# Power.net
KiCad netlist of a schematic drawn in Altium Designer
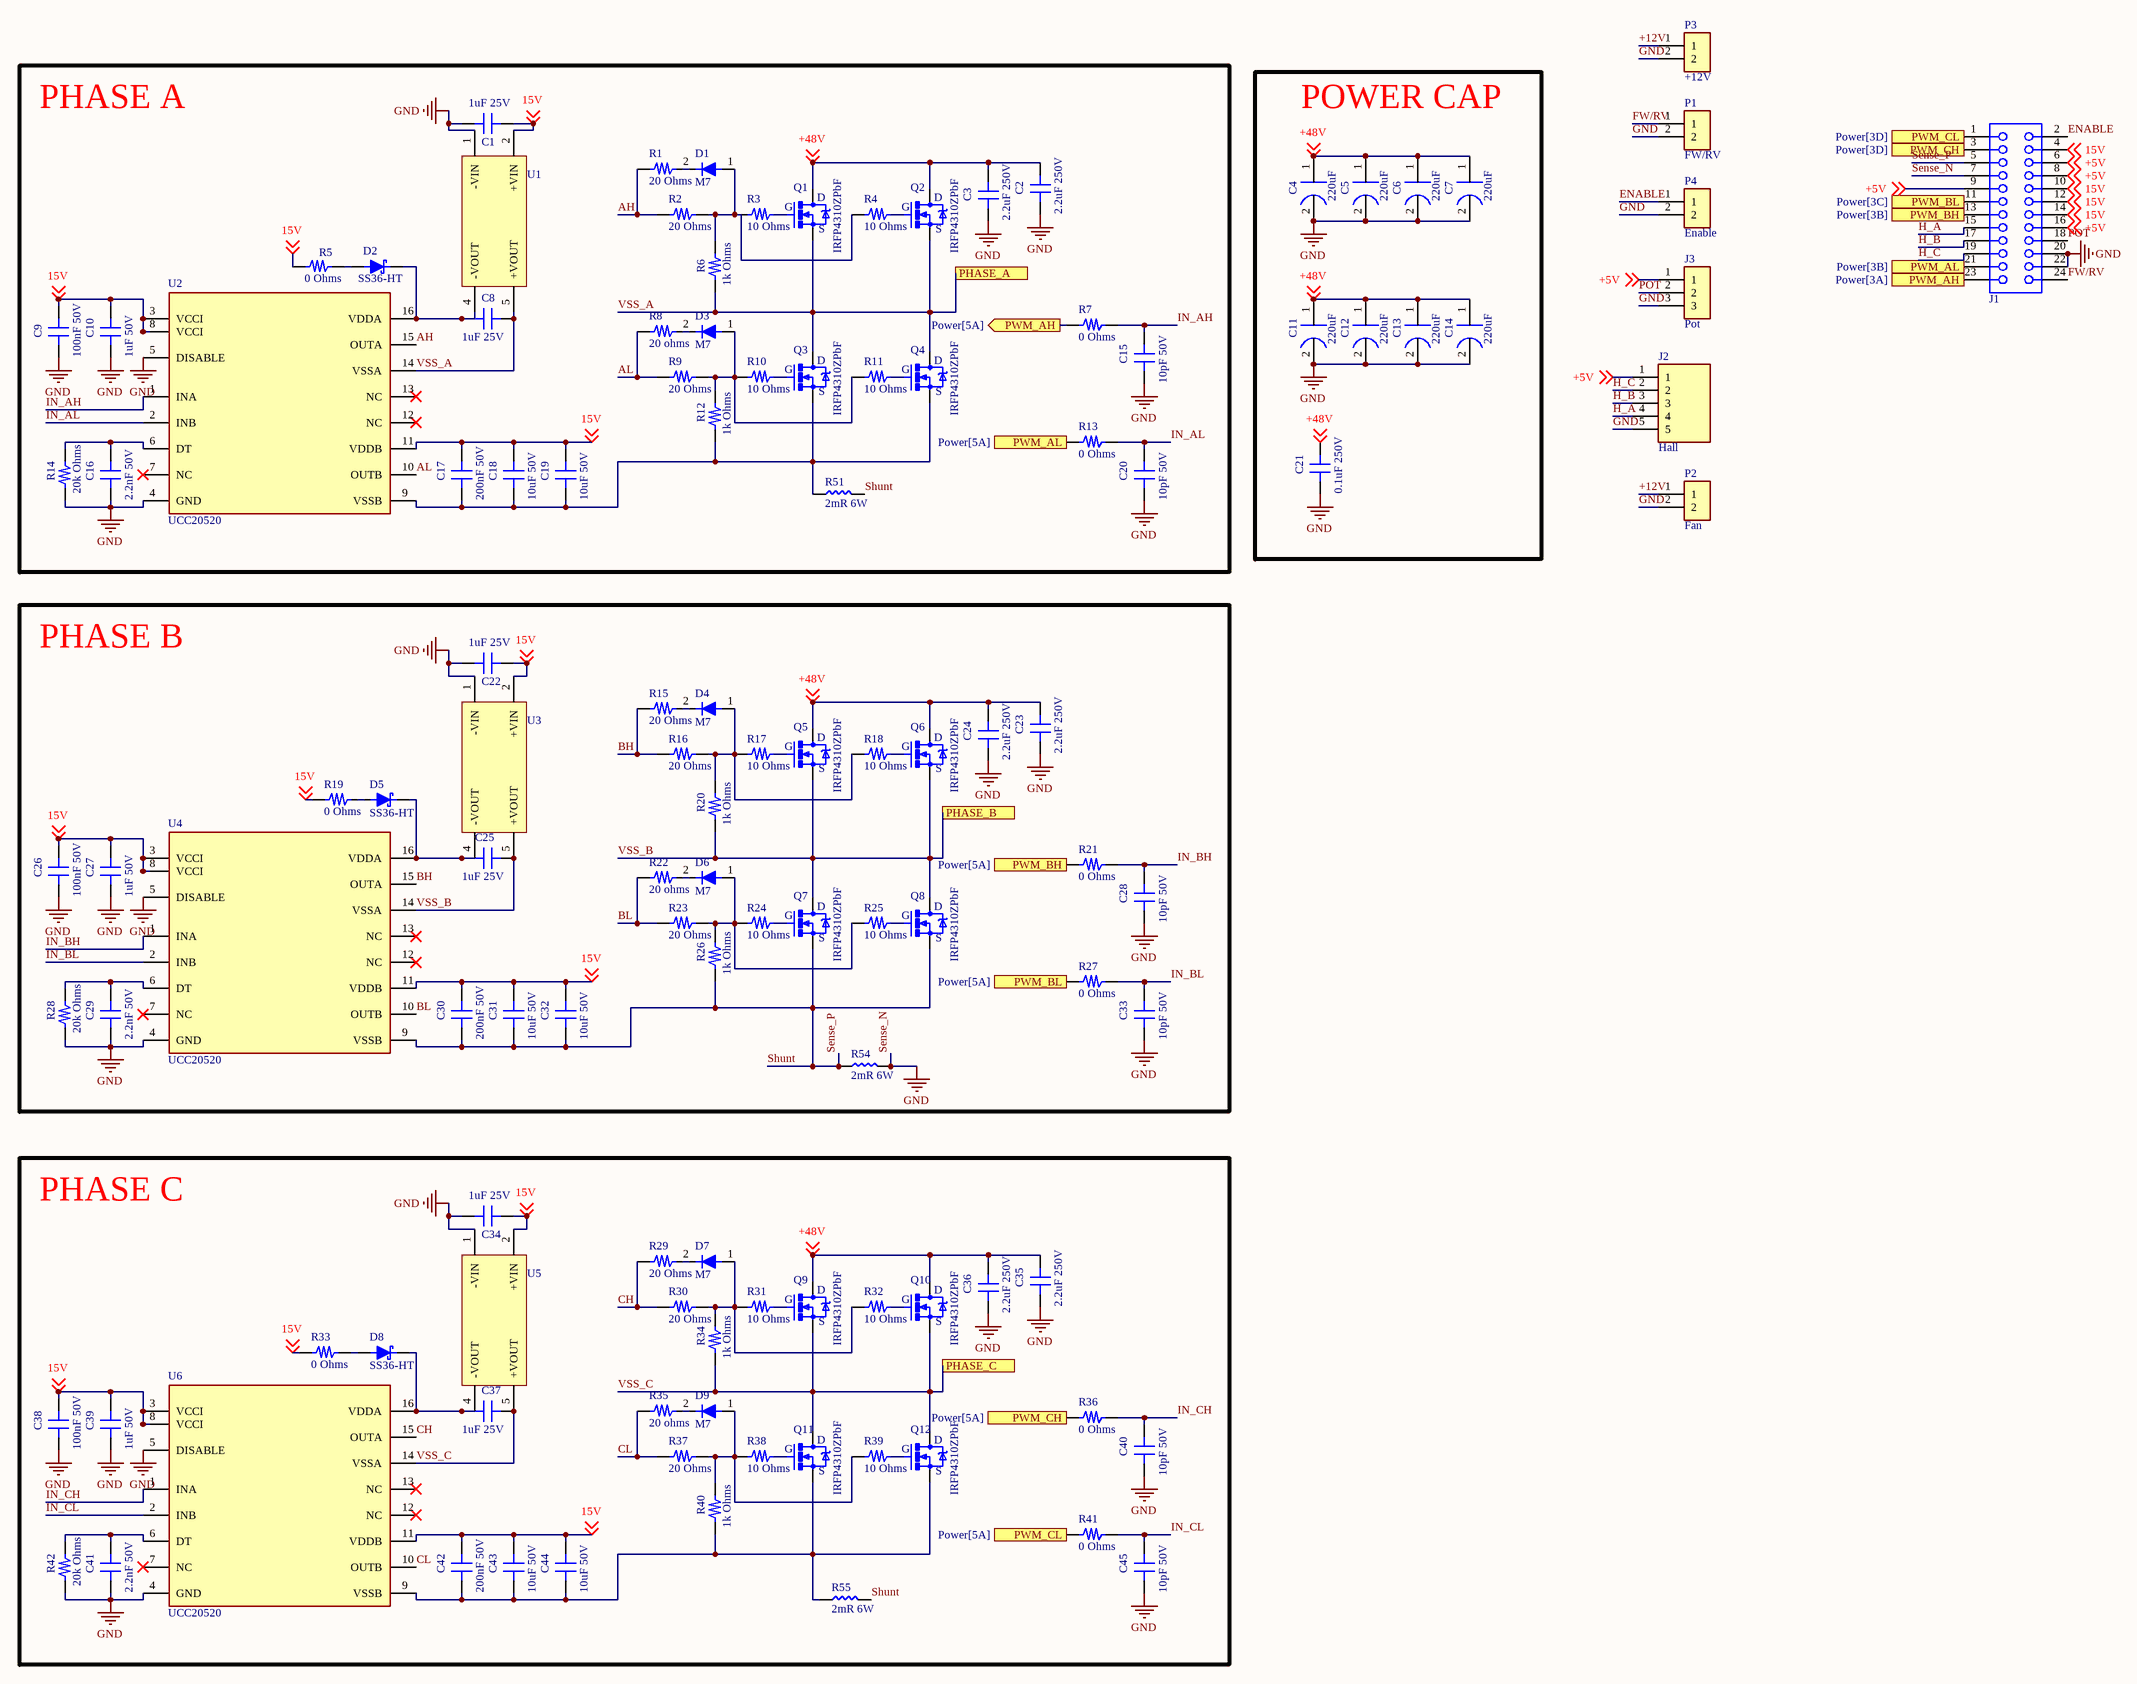
[diagram p0: Power.SchDoc]

(export (version "E")
  (design (tool "Eeschema 10.0.6"))
  (components
    (comp (ref "C1")
      (value "1uF 25V")
      (footprint "0805_CAP")
      (description "1-3.3 uF polyster film cap")
      (libsource (lib "HidroanaSCHLib1") (part "CAP_0805"))
    )
    (comp (ref "C2")
      (value "2.2uF 250V")
      (footprint "0805_CAP")
      (description "MLCC")
      (libsource (lib "HidroanaSCHLib1") (part "CAP_0805"))
    )
    (comp (ref "C3")
      (value "2.2uF 250V")
      (footprint "0805_CAP")
      (description "MLCC")
      (libsource (lib "HidroanaSCHLib1") (part "CAP_0805"))
    )
    (comp (ref "C4")
      (value "220uF")
      (footprint "220uF 100V Cap")
      (libsource (lib "Hidroana Lib") (part "220uF 100V Cap"))
    )
    (comp (ref "C5")
      (value "220uF")
      (footprint "220uF 100V Cap")
      (libsource (lib "Hidroana Lib") (part "220uF 100V Cap"))
    )
    (comp (ref "C6")
      (value "220uF")
      (footprint "220uF 100V Cap")
      (libsource (lib "Hidroana Lib") (part "220uF 100V Cap"))
    )
    (comp (ref "C7")
      (value "220uF")
      (footprint "220uF 100V Cap")
      (libsource (lib "Hidroana Lib") (part "220uF 100V Cap"))
    )
    (comp (ref "C8")
      (value "1uF 25V")
      (footprint "0805_CAP")
      (libsource (lib "HidroanaSCHLib1") (part "CAP_0805"))
    )
    (comp (ref "C9")
      (value "100nF 50V")
      (footprint "0805_CAP")
      (description "MLCC")
      (libsource (lib "HidroanaSCHLib1") (part "CAP_0805"))
    )
    (comp (ref "C10")
      (value "1uF 50V")
      (footprint "0805_CAP")
      (description "tantalum or electrolytic")
      (libsource (lib "HidroanaSCHLib1") (part "CAP_0805"))
    )
    (comp (ref "C11")
      (value "220uF")
      (footprint "220uF 100V Cap")
      (libsource (lib "Hidroana Lib") (part "220uF 100V Cap"))
    )
    (comp (ref "C12")
      (value "220uF")
      (footprint "220uF 100V Cap")
      (libsource (lib "Hidroana Lib") (part "220uF 100V Cap"))
    )
    (comp (ref "C13")
      (value "220uF")
      (footprint "220uF 100V Cap")
      (libsource (lib "Hidroana Lib") (part "220uF 100V Cap"))
    )
    (comp (ref "C14")
      (value "220uF")
      (footprint "220uF 100V Cap")
      (libsource (lib "Hidroana Lib") (part "220uF 100V Cap"))
    )
    (comp (ref "C15")
      (value "10pF 50V")
      (footprint "0805_CAP")
      (description "MLCC 10-100 pF")
      (libsource (lib "HidroanaSCHLib1") (part "CAP_0805"))
    )
    (comp (ref "C16")
      (value "2.2nF 50V")
      (footprint "0805_CAP")
      (libsource (lib "HidroanaSCHLib1") (part "CAP_0805"))
    )
    (comp (ref "C17")
      (value "200nF 50V")
      (footprint "0805_CAP")
      (description "MLCC")
      (libsource (lib "HidroanaSCHLib1") (part "CAP_0805"))
    )
    (comp (ref "C18")
      (value "10uF 50V")
      (footprint "0805_CAP")
      (description "MLCC")
      (libsource (lib "HidroanaSCHLib1") (part "CAP_0805"))
    )
    (comp (ref "C19")
      (value "10uF 50V")
      (footprint "0805_CAP")
      (description "tantalum or electrolytic")
      (libsource (lib "HidroanaSCHLib1") (part "CAP_0805"))
    )
    (comp (ref "C20")
      (value "10pF 50V")
      (footprint "0805_CAP")
      (description "MLCC 10-100 pF")
      (libsource (lib "HidroanaSCHLib1") (part "CAP_0805"))
    )
    (comp (ref "C21")
      (value "0.1uF 250V")
      (footprint "0805_CAP")
      (description "MLCC")
      (libsource (lib "HidroanaSCHLib1") (part "CAP_0805"))
    )
    (comp (ref "C22")
      (value "1uF 25V")
      (footprint "0805_CAP")
      (description "1-3.3 uF polyster film cap")
      (libsource (lib "HidroanaSCHLib1") (part "CAP_0805"))
    )
    (comp (ref "C23")
      (value "2.2uF 250V")
      (footprint "0805_CAP")
      (description "MLCC")
      (libsource (lib "HidroanaSCHLib1") (part "CAP_0805"))
    )
    (comp (ref "C24")
      (value "2.2uF 250V")
      (footprint "0805_CAP")
      (description "MLCC")
      (libsource (lib "HidroanaSCHLib1") (part "CAP_0805"))
    )
    (comp (ref "C25")
      (value "1uF 25V")
      (footprint "0805_CAP")
      (libsource (lib "HidroanaSCHLib1") (part "CAP_0805"))
    )
    (comp (ref "C26")
      (value "100nF 50V")
      (footprint "0805_CAP")
      (description "MLCC")
      (libsource (lib "HidroanaSCHLib1") (part "CAP_0805"))
    )
    (comp (ref "C27")
      (value "1uF 50V")
      (footprint "0805_CAP")
      (description "tantalum or electrolytic")
      (libsource (lib "HidroanaSCHLib1") (part "CAP_0805"))
    )
    (comp (ref "C28")
      (value "10pF 50V")
      (footprint "0805_CAP")
      (description "MLCC 10-100 pF")
      (libsource (lib "HidroanaSCHLib1") (part "CAP_0805"))
    )
    (comp (ref "C29")
      (value "2.2nF 50V")
      (footprint "0805_CAP")
      (libsource (lib "HidroanaSCHLib1") (part "CAP_0805"))
    )
    (comp (ref "C30")
      (value "200nF 50V")
      (footprint "0805_CAP")
      (description "MLCC")
      (libsource (lib "HidroanaSCHLib1") (part "CAP_0805"))
    )
    (comp (ref "C31")
      (value "10uF 50V")
      (footprint "0805_CAP")
      (description "MLCC")
      (libsource (lib "HidroanaSCHLib1") (part "CAP_0805"))
    )
    (comp (ref "C32")
      (value "10uF 50V")
      (footprint "0805_CAP")
      (description "tantalum or electrolytic")
      (libsource (lib "HidroanaSCHLib1") (part "CAP_0805"))
    )
    (comp (ref "C33")
      (value "10pF 50V")
      (footprint "0805_CAP")
      (description "MLCC 10-100 pF")
      (libsource (lib "HidroanaSCHLib1") (part "CAP_0805"))
    )
    (comp (ref "C34")
      (value "1uF 25V")
      (footprint "0805_CAP")
      (description "1-3.3 uF polyster film cap")
      (libsource (lib "HidroanaSCHLib1") (part "CAP_0805"))
    )
    (comp (ref "C35")
      (value "2.2uF 250V")
      (footprint "0805_CAP")
      (description "MLCC")
      (libsource (lib "HidroanaSCHLib1") (part "CAP_0805"))
    )
    (comp (ref "C36")
      (value "2.2uF 250V")
      (footprint "0805_CAP")
      (description "MLCC")
      (libsource (lib "HidroanaSCHLib1") (part "CAP_0805"))
    )
    (comp (ref "C37")
      (value "1uF 25V")
      (footprint "0805_CAP")
      (libsource (lib "HidroanaSCHLib1") (part "CAP_0805"))
    )
    (comp (ref "C38")
      (value "100nF 50V")
      (footprint "0805_CAP")
      (description "MLCC")
      (libsource (lib "HidroanaSCHLib1") (part "CAP_0805"))
    )
    (comp (ref "C39")
      (value "1uF 50V")
      (footprint "0805_CAP")
      (description "tantalum or electrolytic")
      (libsource (lib "HidroanaSCHLib1") (part "CAP_0805"))
    )
    (comp (ref "C40")
      (value "10pF 50V")
      (footprint "0805_CAP")
      (description "MLCC 10-100 pF")
      (libsource (lib "HidroanaSCHLib1") (part "CAP_0805"))
    )
    (comp (ref "C41")
      (value "2.2nF 50V")
      (footprint "0805_CAP")
      (libsource (lib "HidroanaSCHLib1") (part "CAP_0805"))
    )
    (comp (ref "C42")
      (value "200nF 50V")
      (footprint "0805_CAP")
      (description "MLCC")
      (libsource (lib "HidroanaSCHLib1") (part "CAP_0805"))
    )
    (comp (ref "C43")
      (value "10uF 50V")
      (footprint "0805_CAP")
      (description "MLCC")
      (libsource (lib "HidroanaSCHLib1") (part "CAP_0805"))
    )
    (comp (ref "C44")
      (value "10uF 50V")
      (footprint "0805_CAP")
      (description "tantalum or electrolytic")
      (libsource (lib "HidroanaSCHLib1") (part "CAP_0805"))
    )
    (comp (ref "C45")
      (value "10pF 50V")
      (footprint "0805_CAP")
      (description "MLCC 10-100 pF")
      (libsource (lib "HidroanaSCHLib1") (part "CAP_0805"))
    )
    (comp (ref "D1")
      (value "M7")
      (footprint "DIOM5025X220N")
      (description "M7-DC - DIODE STAND. Single 1A 1000V SMT DO214AC (SMA)")
      (libsource (lib "HidroanaSCHLib1") (part "M7"))
    )
    (comp (ref "D2")
      (value "SS36-HT")
      (footprint "DO-214AB")
      (description "Schottky Diode")
      (libsource (lib "HidroanaSCHLib1") (part "SS36-214AB-HT"))
    )
    (comp (ref "D3")
      (value "M7")
      (footprint "DIOM5025X220N")
      (description "M7-DC - DIODE STAND. Single 1A 1000V SMT DO214AC (SMA)")
      (libsource (lib "HidroanaSCHLib1") (part "M7"))
    )
    (comp (ref "D4")
      (value "M7")
      (footprint "DIOM5025X220N")
      (description "M7-DC - DIODE STAND. Single 1A 1000V SMT DO214AC (SMA)")
      (libsource (lib "HidroanaSCHLib1") (part "M7"))
    )
    (comp (ref "D5")
      (value "SS36-HT")
      (footprint "DO-214AB")
      (description "Schottky Diode")
      (libsource (lib "HidroanaSCHLib1") (part "SS36-214AB-HT"))
    )
    (comp (ref "D6")
      (value "M7")
      (footprint "DIOM5025X220N")
      (description "M7-DC - DIODE STAND. Single 1A 1000V SMT DO214AC (SMA)")
      (libsource (lib "HidroanaSCHLib1") (part "M7"))
    )
    (comp (ref "D7")
      (value "M7")
      (footprint "DIOM5025X220N")
      (description "M7-DC - DIODE STAND. Single 1A 1000V SMT DO214AC (SMA)")
      (libsource (lib "HidroanaSCHLib1") (part "M7"))
    )
    (comp (ref "D8")
      (value "SS36-HT")
      (footprint "DO-214AB")
      (description "Schottky Diode")
      (libsource (lib "HidroanaSCHLib1") (part "SS36-214AB-HT"))
    )
    (comp (ref "D9")
      (value "M7")
      (footprint "DIOM5025X220N")
      (description "M7-DC - DIODE STAND. Single 1A 1000V SMT DO214AC (SMA)")
      (libsource (lib "HidroanaSCHLib1") (part "M7"))
    )
    (comp (ref "J1")
      (value "61302421821")
      (footprint "61302421821")
      (description "WR-PHD Socket Header, THT, Vertical, pitch 2.54mm, 2 Row, 24P")
      (fields (field (name "MANUFACTURER") "Wurth Elektronik"))
      (libsource (lib "Altium_WR-PHD (rev24a) (1)") (part "61302421821"))
    )
    (comp (ref "J2")
      (value "Hall")
      (footprint "TE_282837-5")
      (description "TERMI-BLOK PCB MOUNT 5P")
      (fields (field (name "MP") "282837-5") (field (name "MF") "TE Connectivity"))
      (libsource (lib "TBLOCK-I5") (part "282837-5"))
    )
    (comp (ref "J3")
      (value "Pot")
      (footprint "TE_282837-3")
      (description "TERMI-BLOK PCB MOUNT 3P")
      (fields (field (name "MP") "282837-3"))
      (libsource (lib "TBLOCK-I3") (part "282837-3"))
    )
    (comp (ref "P1")
      (value "FW/RV")
      (footprint "TE_282837-2")
      (fields (field (name "MF") "TE Connectivity") (field (name "MP") "282837-2"))
      (libsource (lib "TBLOCK-I2") (part "282837-2"))
    )
    (comp (ref "P2")
      (value "Fan")
      (footprint "TE_282837-2")
      (fields (field (name "MF") "TE Connectivity") (field (name "MP") "282837-2"))
      (libsource (lib "TBLOCK-I2") (part "282837-2"))
    )
    (comp (ref "P3")
      (value "+12V")
      (footprint "TE_282837-2")
      (fields (field (name "MF") "TE Connectivity") (field (name "MP") "282837-2"))
      (libsource (lib "TBLOCK-I2") (part "282837-2"))
    )
    (comp (ref "P4")
      (value "Enable")
      (footprint "TE_282837-2")
      (fields (field (name "MF") "TE Connectivity") (field (name "MP") "282837-2"))
      (libsource (lib "TBLOCK-I2") (part "282837-2"))
    )
    (comp (ref "Q1")
      (value "IRFP4310ZPbF")
      (footprint "TO-247")
      (description "IRFP4310ZPBF - MOSFET DIS.120A 100V N-CH TO247AC HEXFET THT")
      (libsource (lib "HidroanaSCHLib1") (part "IRFP4310ZPbF"))
    )
    (comp (ref "Q2")
      (value "IRFP4310ZPbF")
      (footprint "TO-247")
      (description "IRFP4310ZPBF - MOSFET DIS.120A 100V N-CH TO247AC HEXFET THT")
      (libsource (lib "HidroanaSCHLib1") (part "IRFP4310ZPbF"))
    )
    (comp (ref "Q3")
      (value "IRFP4310ZPbF")
      (footprint "TO-247")
      (description "IRFP4310ZPBF - MOSFET DIS.120A 100V N-CH TO247AC HEXFET THT")
      (libsource (lib "HidroanaSCHLib1") (part "IRFP4310ZPbF"))
    )
    (comp (ref "Q4")
      (value "IRFP4310ZPbF")
      (footprint "TO-247")
      (description "IRFP4310ZPBF - MOSFET DIS.120A 100V N-CH TO247AC HEXFET THT")
      (libsource (lib "HidroanaSCHLib1") (part "IRFP4310ZPbF"))
    )
    (comp (ref "Q5")
      (value "IRFP4310ZPbF")
      (footprint "TO-247")
      (description "IRFP4310ZPBF - MOSFET DIS.120A 100V N-CH TO247AC HEXFET THT")
      (libsource (lib "HidroanaSCHLib1") (part "IRFP4310ZPbF"))
    )
    (comp (ref "Q6")
      (value "IRFP4310ZPbF")
      (footprint "TO-247")
      (description "IRFP4310ZPBF - MOSFET DIS.120A 100V N-CH TO247AC HEXFET THT")
      (libsource (lib "HidroanaSCHLib1") (part "IRFP4310ZPbF"))
    )
    (comp (ref "Q7")
      (value "IRFP4310ZPbF")
      (footprint "TO-247")
      (description "IRFP4310ZPBF - MOSFET DIS.120A 100V N-CH TO247AC HEXFET THT")
      (libsource (lib "HidroanaSCHLib1") (part "IRFP4310ZPbF"))
    )
    (comp (ref "Q8")
      (value "IRFP4310ZPbF")
      (footprint "TO-247")
      (description "IRFP4310ZPBF - MOSFET DIS.120A 100V N-CH TO247AC HEXFET THT")
      (libsource (lib "HidroanaSCHLib1") (part "IRFP4310ZPbF"))
    )
    (comp (ref "Q9")
      (value "IRFP4310ZPbF")
      (footprint "TO-247")
      (description "IRFP4310ZPBF - MOSFET DIS.120A 100V N-CH TO247AC HEXFET THT")
      (libsource (lib "HidroanaSCHLib1") (part "IRFP4310ZPbF"))
    )
    (comp (ref "Q10")
      (value "IRFP4310ZPbF")
      (footprint "TO-247")
      (description "IRFP4310ZPBF - MOSFET DIS.120A 100V N-CH TO247AC HEXFET THT")
      (libsource (lib "HidroanaSCHLib1") (part "IRFP4310ZPbF"))
    )
    (comp (ref "Q11")
      (value "IRFP4310ZPbF")
      (footprint "TO-247")
      (description "IRFP4310ZPBF - MOSFET DIS.120A 100V N-CH TO247AC HEXFET THT")
      (libsource (lib "HidroanaSCHLib1") (part "IRFP4310ZPbF"))
    )
    (comp (ref "Q12")
      (value "IRFP4310ZPbF")
      (footprint "TO-247")
      (description "IRFP4310ZPBF - MOSFET DIS.120A 100V N-CH TO247AC HEXFET THT")
      (libsource (lib "HidroanaSCHLib1") (part "IRFP4310ZPbF"))
    )
    (comp (ref "R1")
      (value "20 Ohms")
      (footprint "0805_RES")
      (description "0805")
      (fields (field (name "POWER") "1/8 W"))
      (libsource (lib "HidroanaSCHLib1") (part "RES_0805"))
    )
    (comp (ref "R2")
      (value "20 Ohms")
      (footprint "0805_RES")
      (description "0805")
      (fields (field (name "POWER") "1/8 W"))
      (libsource (lib "HidroanaSCHLib1") (part "RES_0805"))
    )
    (comp (ref "R3")
      (value "10 Ohms")
      (footprint "0805_RES")
      (description "0805")
      (fields (field (name "POWER") "1/8 W"))
      (libsource (lib "HidroanaSCHLib1") (part "RES_0805"))
    )
    (comp (ref "R4")
      (value "10 Ohms")
      (footprint "0805_RES")
      (description "0805")
      (fields (field (name "POWER") "1/8 W"))
      (libsource (lib "HidroanaSCHLib1") (part "RES_0805"))
    )
    (comp (ref "R5")
      (value "0 Ohms")
      (footprint "0805_RES")
      (description "0805                                                      1-20 ohms")
      (fields (field (name "POWER") "1/8 W"))
      (libsource (lib "HidroanaSCHLib1") (part "RES_0805"))
    )
    (comp (ref "R6")
      (value "1k Ohms")
      (footprint "0805_RES")
      (description "0805")
      (fields (field (name "POWER") "1/8 W"))
      (libsource (lib "HidroanaSCHLib1") (part "RES_0805"))
    )
    (comp (ref "R7")
      (value "0 Ohms")
      (footprint "0805_RES")
      (description "0805 0-100 OHMS")
      (fields (field (name "POWER") "1/8 W"))
      (libsource (lib "HidroanaSCHLib1") (part "RES_0805"))
    )
    (comp (ref "R8")
      (value "20 ohms")
      (footprint "0805_RES")
      (description "0805")
      (fields (field (name "POWER") "1/8 W"))
      (libsource (lib "HidroanaSCHLib1") (part "RES_0805"))
    )
    (comp (ref "R9")
      (value "20 Ohms")
      (footprint "0805_RES")
      (description "0805")
      (fields (field (name "POWER") "1/8 W"))
      (libsource (lib "HidroanaSCHLib1") (part "RES_0805"))
    )
    (comp (ref "R10")
      (value "10 Ohms")
      (footprint "0805_RES")
      (description "0805")
      (fields (field (name "POWER") "1/8 W"))
      (libsource (lib "HidroanaSCHLib1") (part "RES_0805"))
    )
    (comp (ref "R11")
      (value "10 Ohms")
      (footprint "0805_RES")
      (description "0805")
      (fields (field (name "POWER") "1/8 W"))
      (libsource (lib "HidroanaSCHLib1") (part "RES_0805"))
    )
    (comp (ref "R12")
      (value "1k Ohms")
      (footprint "0805_RES")
      (description "0805")
      (fields (field (name "POWER") "1/8 W"))
      (libsource (lib "HidroanaSCHLib1") (part "RES_0805"))
    )
    (comp (ref "R13")
      (value "0 Ohms")
      (footprint "0805_RES")
      (description "0805 0-100 OHMS")
      (fields (field (name "POWER") "1/8 W"))
      (libsource (lib "HidroanaSCHLib1") (part "RES_0805"))
    )
    (comp (ref "R14")
      (value "20k Ohms")
      (footprint "0805_RES")
      (description "0805")
      (fields (field (name "POWER") "1/8 W"))
      (libsource (lib "HidroanaSCHLib1") (part "RES_0805"))
    )
    (comp (ref "R15")
      (value "20 Ohms")
      (footprint "0805_RES")
      (description "0805")
      (fields (field (name "POWER") "1/8 W"))
      (libsource (lib "HidroanaSCHLib1") (part "RES_0805"))
    )
    (comp (ref "R16")
      (value "20 Ohms")
      (footprint "0805_RES")
      (description "0805")
      (fields (field (name "POWER") "1/8 W"))
      (libsource (lib "HidroanaSCHLib1") (part "RES_0805"))
    )
    (comp (ref "R17")
      (value "10 Ohms")
      (footprint "0805_RES")
      (description "0805")
      (fields (field (name "POWER") "1/8 W"))
      (libsource (lib "HidroanaSCHLib1") (part "RES_0805"))
    )
    (comp (ref "R18")
      (value "10 Ohms")
      (footprint "0805_RES")
      (description "0805")
      (fields (field (name "POWER") "1/8 W"))
      (libsource (lib "HidroanaSCHLib1") (part "RES_0805"))
    )
    (comp (ref "R19")
      (value "0 Ohms")
      (footprint "0805_RES")
      (description "0805                                                      1-20 ohms")
      (fields (field (name "POWER") "1/8 W"))
      (libsource (lib "HidroanaSCHLib1") (part "RES_0805"))
    )
    (comp (ref "R20")
      (value "1k Ohms")
      (footprint "0805_RES")
      (description "0805")
      (fields (field (name "POWER") "1/8 W"))
      (libsource (lib "HidroanaSCHLib1") (part "RES_0805"))
    )
    (comp (ref "R21")
      (value "0 Ohms")
      (footprint "0805_RES")
      (description "0805 0-100 OHMS")
      (fields (field (name "POWER") "1/8 W"))
      (libsource (lib "HidroanaSCHLib1") (part "RES_0805"))
    )
    (comp (ref "R22")
      (value "20 ohms")
      (footprint "0805_RES")
      (description "0805")
      (fields (field (name "POWER") "1/8 W"))
      (libsource (lib "HidroanaSCHLib1") (part "RES_0805"))
    )
    (comp (ref "R23")
      (value "20 Ohms")
      (footprint "0805_RES")
      (description "0805")
      (fields (field (name "POWER") "1/8 W"))
      (libsource (lib "HidroanaSCHLib1") (part "RES_0805"))
    )
    (comp (ref "R24")
      (value "10 Ohms")
      (footprint "0805_RES")
      (description "0805")
      (fields (field (name "POWER") "1/8 W"))
      (libsource (lib "HidroanaSCHLib1") (part "RES_0805"))
    )
    (comp (ref "R25")
      (value "10 Ohms")
      (footprint "0805_RES")
      (description "0805")
      (fields (field (name "POWER") "1/8 W"))
      (libsource (lib "HidroanaSCHLib1") (part "RES_0805"))
    )
    (comp (ref "R26")
      (value "1k Ohms")
      (footprint "0805_RES")
      (description "0805")
      (fields (field (name "POWER") "1/8 W"))
      (libsource (lib "HidroanaSCHLib1") (part "RES_0805"))
    )
    (comp (ref "R27")
      (value "0 Ohms")
      (footprint "0805_RES")
      (description "0805 0-100 OHMS")
      (fields (field (name "POWER") "1/8 W"))
      (libsource (lib "HidroanaSCHLib1") (part "RES_0805"))
    )
    (comp (ref "R28")
      (value "20k Ohms")
      (footprint "0805_RES")
      (description "0805")
      (fields (field (name "POWER") "1/8 W"))
      (libsource (lib "HidroanaSCHLib1") (part "RES_0805"))
    )
    (comp (ref "R29")
      (value "20 Ohms")
      (footprint "0805_RES")
      (description "0805")
      (fields (field (name "POWER") "1/8 W"))
      (libsource (lib "HidroanaSCHLib1") (part "RES_0805"))
    )
    (comp (ref "R30")
      (value "20 Ohms")
      (footprint "0805_RES")
      (description "0805")
      (fields (field (name "POWER") "1/8 W"))
      (libsource (lib "HidroanaSCHLib1") (part "RES_0805"))
    )
    (comp (ref "R31")
      (value "10 Ohms")
      (footprint "0805_RES")
      (description "0805")
      (fields (field (name "POWER") "1/8 W"))
      (libsource (lib "HidroanaSCHLib1") (part "RES_0805"))
    )
    (comp (ref "R32")
      (value "10 Ohms")
      (footprint "0805_RES")
      (description "0805")
      (fields (field (name "POWER") "1/8 W"))
      (libsource (lib "HidroanaSCHLib1") (part "RES_0805"))
    )
    (comp (ref "R33")
      (value "0 Ohms")
      (footprint "0805_RES")
      (description "0805                                                      1-20 ohms")
      (fields (field (name "POWER") "1/8 W"))
      (libsource (lib "HidroanaSCHLib1") (part "RES_0805"))
    )
    (comp (ref "R34")
      (value "1k Ohms")
      (footprint "0805_RES")
      (description "0805")
      (fields (field (name "POWER") "1/8 W"))
      (libsource (lib "HidroanaSCHLib1") (part "RES_0805"))
    )
    (comp (ref "R35")
      (value "20 ohms")
      (footprint "0805_RES")
      (description "0805")
      (fields (field (name "POWER") "1/8 W"))
      (libsource (lib "HidroanaSCHLib1") (part "RES_0805"))
    )
    (comp (ref "R36")
      (value "0 Ohms")
      (footprint "0805_RES")
      (description "0805 0-100 OHMS")
      (fields (field (name "POWER") "1/8 W"))
      (libsource (lib "HidroanaSCHLib1") (part "RES_0805"))
    )
    (comp (ref "R37")
      (value "20 Ohms")
      (footprint "0805_RES")
      (description "0805")
      (fields (field (name "POWER") "1/8 W"))
      (libsource (lib "HidroanaSCHLib1") (part "RES_0805"))
    )
    (comp (ref "R38")
      (value "10 Ohms")
      (footprint "0805_RES")
      (description "0805")
      (fields (field (name "POWER") "1/8 W"))
      (libsource (lib "HidroanaSCHLib1") (part "RES_0805"))
    )
    (comp (ref "R39")
      (value "10 Ohms")
      (footprint "0805_RES")
      (description "0805")
      (fields (field (name "POWER") "1/8 W"))
      (libsource (lib "HidroanaSCHLib1") (part "RES_0805"))
    )
    (comp (ref "R40")
      (value "1k Ohms")
      (footprint "0805_RES")
      (description "0805")
      (fields (field (name "POWER") "1/8 W"))
      (libsource (lib "HidroanaSCHLib1") (part "RES_0805"))
    )
    (comp (ref "R41")
      (value "0 Ohms")
      (footprint "0805_RES")
      (description "0805 0-100 OHMS")
      (fields (field (name "POWER") "1/8 W"))
      (libsource (lib "HidroanaSCHLib1") (part "RES_0805"))
    )
    (comp (ref "R42")
      (value "20k Ohms")
      (footprint "0805_RES")
      (description "0805")
      (fields (field (name "POWER") "1/8 W"))
      (libsource (lib "HidroanaSCHLib1") (part "RES_0805"))
    )
    (comp (ref "R51")
      (value "2mR 6W")
      (footprint "3920")
      (description "3920")
      (libsource (lib "Hidroana Lib") (part "Shunt"))
    )
    (comp (ref "R54")
      (value "2mR 6W")
      (footprint "3920")
      (description "3920")
      (libsource (lib "Hidroana Lib") (part "Shunt"))
    )
    (comp (ref "R55")
      (value "2mR 6W")
      (footprint "3920")
      (description "3920")
      (libsource (lib "Hidroana Lib") (part "Shunt"))
    )
    (comp (ref "U1")
      (value "5Vin, 15Vout")
      (footprint "WPME-FISM_SMT-8_L12.75W10.7H6.95")
      (description "WPME-FISM Fixed Isolated Module, SMT-8, 5Vin, 15Vout")
      (fields
        (field (name "MANUFACTURER PART NUMBER") "176861512")
        (field (name "MANUFACTURER") "Wurth Elektronik")
      )
      (libsource (lib "Altium_WPME-FISM (rev23a)") (part "176861512"))
    )
    (comp (ref "U2")
      (value "UCC20520")
      (footprint "UCC20520")
      (libsource (lib "HidroanaSCHLib1") (part "UCC21520"))
    )
    (comp (ref "U3")
      (value "5Vin, 15Vout")
      (footprint "WPME-FISM_SMT-8_L12.75W10.7H6.95")
      (description "WPME-FISM Fixed Isolated Module, SMT-8, 5Vin, 15Vout")
      (fields
        (field (name "MANUFACTURER PART NUMBER") "176861512")
        (field (name "MANUFACTURER") "Wurth Elektronik")
      )
      (libsource (lib "Altium_WPME-FISM (rev23a)") (part "176861512"))
    )
    (comp (ref "U4")
      (value "UCC20520")
      (footprint "UCC20520")
      (libsource (lib "HidroanaSCHLib1") (part "UCC21520"))
    )
    (comp (ref "U5")
      (value "5Vin, 15Vout")
      (footprint "WPME-FISM_SMT-8_L12.75W10.7H6.95")
      (description "WPME-FISM Fixed Isolated Module, SMT-8, 5Vin, 15Vout")
      (fields
        (field (name "MANUFACTURER PART NUMBER") "176861512")
        (field (name "MANUFACTURER") "Wurth Elektronik")
      )
      (libsource (lib "Altium_WPME-FISM (rev23a)") (part "176861512"))
    )
    (comp (ref "U6")
      (value "UCC20520")
      (footprint "UCC20520")
      (libsource (lib "HidroanaSCHLib1") (part "UCC21520"))
    )
  )
  (nets
    (net (code "1") (name "+5V") (class "Default")
      (node (ref "J1") (pin "16") (pinfunction "16_16") (pintype "passive"))
      (node (ref "J1") (pin "6") (pinfunction "6_6") (pintype "passive"))
      (node (ref "J1") (pin "8") (pinfunction "8_8") (pintype "passive"))
      (node (ref "J1") (pin "9") (pinfunction "9_9") (pintype "passive"))
      (node (ref "J2") (pin "1") (pinfunction "1_1") (pintype "passive"))
      (node (ref "J3") (pin "1") (pinfunction "1_1") (pintype "passive"))
    )
    (net (code "2") (name "+48V") (class "Default")
      (node (ref "C11") (pin "1") (pinfunction "1_1") (pintype "passive"))
      (node (ref "C12") (pin "1") (pinfunction "1_1") (pintype "passive"))
      (node (ref "C13") (pin "1") (pinfunction "1_1") (pintype "passive"))
      (node (ref "C14") (pin "1") (pinfunction "1_1") (pintype "passive"))
      (node (ref "C2") (pin "2") (pinfunction "2_2") (pintype "passive"))
      (node (ref "C21") (pin "2") (pinfunction "2_2") (pintype "passive"))
      (node (ref "C23") (pin "2") (pinfunction "2_2") (pintype "passive"))
      (node (ref "C24") (pin "2") (pinfunction "2_2") (pintype "passive"))
      (node (ref "C3") (pin "2") (pinfunction "2_2") (pintype "passive"))
      (node (ref "C35") (pin "2") (pinfunction "2_2") (pintype "passive"))
      (node (ref "C36") (pin "2") (pinfunction "2_2") (pintype "passive"))
      (node (ref "C4") (pin "1") (pinfunction "1_1") (pintype "passive"))
      (node (ref "C5") (pin "1") (pinfunction "1_1") (pintype "passive"))
      (node (ref "C6") (pin "1") (pinfunction "1_1") (pintype "passive"))
      (node (ref "C7") (pin "1") (pinfunction "1_1") (pintype "passive"))
      (node (ref "Q1") (pin "2") (pinfunction "D_2") (pintype "passive"))
      (node (ref "Q10") (pin "2") (pinfunction "D_2") (pintype "passive"))
      (node (ref "Q2") (pin "2") (pinfunction "D_2") (pintype "passive"))
      (node (ref "Q5") (pin "2") (pinfunction "D_2") (pintype "passive"))
      (node (ref "Q6") (pin "2") (pinfunction "D_2") (pintype "passive"))
      (node (ref "Q9") (pin "2") (pinfunction "D_2") (pintype "passive"))
    )
    (net (code "3") (name "/+12V") (class "Default")
      (node (ref "P2") (pin "1") (pinfunction "1_1") (pintype "passive"))
      (node (ref "P3") (pin "1") (pinfunction "1_1") (pintype "passive"))
    )
    (net (code "4") (name "/AH") (class "Default")
      (node (ref "R1") (pin "1") (pintype "passive"))
      (node (ref "R2") (pin "1") (pintype "passive"))
      (node (ref "U2") (pin "15") (pinfunction "OUTA_15") (pintype "passive"))
    )
    (net (code "5") (name "/AL") (class "Default")
      (node (ref "R8") (pin "1") (pintype "passive"))
      (node (ref "R9") (pin "1") (pintype "passive"))
      (node (ref "U2") (pin "10") (pinfunction "OUTB_10") (pintype "passive"))
    )
    (net (code "6") (name "/BH") (class "Default")
      (node (ref "R15") (pin "1") (pintype "passive"))
      (node (ref "R16") (pin "1") (pintype "passive"))
      (node (ref "U4") (pin "15") (pinfunction "OUTA_15") (pintype "passive"))
    )
    (net (code "7") (name "/BL") (class "Default")
      (node (ref "R22") (pin "1") (pintype "passive"))
      (node (ref "R23") (pin "1") (pintype "passive"))
      (node (ref "U4") (pin "10") (pinfunction "OUTB_10") (pintype "passive"))
    )
    (net (code "8") (name "/CH") (class "Default")
      (node (ref "R29") (pin "1") (pintype "passive"))
      (node (ref "R30") (pin "1") (pintype "passive"))
      (node (ref "U6") (pin "15") (pinfunction "OUTA_15") (pintype "passive"))
    )
    (net (code "9") (name "/CL") (class "Default")
      (node (ref "R35") (pin "1") (pintype "passive"))
      (node (ref "R37") (pin "1") (pintype "passive"))
      (node (ref "U6") (pin "10") (pinfunction "OUTB_10") (pintype "passive"))
    )
    (net (code "10") (name "/ENABLE") (class "Default")
      (node (ref "J1") (pin "2") (pinfunction "2_2") (pintype "passive"))
      (node (ref "P4") (pin "1") (pinfunction "1_1") (pintype "passive"))
    )
    (net (code "11") (name "/FW{slash}RV") (class "Default")
      (node (ref "J1") (pin "24") (pinfunction "24_24") (pintype "passive"))
      (node (ref "P1") (pin "1") (pinfunction "1_1") (pintype "passive"))
    )
    (net (code "12") (name "/H_A") (class "Default")
      (node (ref "J1") (pin "15") (pinfunction "15_15") (pintype "passive"))
      (node (ref "J2") (pin "4") (pinfunction "4_4") (pintype "passive"))
    )
    (net (code "13") (name "/H_B") (class "Default")
      (node (ref "J1") (pin "17") (pinfunction "17_17") (pintype "passive"))
      (node (ref "J2") (pin "3") (pinfunction "3_3") (pintype "passive"))
    )
    (net (code "14") (name "/H_C") (class "Default")
      (node (ref "J1") (pin "19") (pinfunction "19_19") (pintype "passive"))
      (node (ref "J2") (pin "2") (pinfunction "2_2") (pintype "passive"))
    )
    (net (code "15") (name "/IN_AH") (class "Default")
      (node (ref "C15") (pin "2") (pinfunction "2_2") (pintype "passive"))
      (node (ref "R7") (pin "2") (pintype "passive"))
      (node (ref "U2") (pin "1") (pinfunction "INA_1") (pintype "passive"))
    )
    (net (code "16") (name "/IN_AL") (class "Default")
      (node (ref "C20") (pin "2") (pinfunction "2_2") (pintype "passive"))
      (node (ref "R13") (pin "2") (pintype "passive"))
      (node (ref "U2") (pin "2") (pinfunction "INB_2") (pintype "passive"))
    )
    (net (code "17") (name "/IN_BH") (class "Default")
      (node (ref "C28") (pin "2") (pinfunction "2_2") (pintype "passive"))
      (node (ref "R21") (pin "2") (pintype "passive"))
      (node (ref "U4") (pin "1") (pinfunction "INA_1") (pintype "passive"))
    )
    (net (code "18") (name "/IN_BL") (class "Default")
      (node (ref "C33") (pin "2") (pinfunction "2_2") (pintype "passive"))
      (node (ref "R27") (pin "2") (pintype "passive"))
      (node (ref "U4") (pin "2") (pinfunction "INB_2") (pintype "passive"))
    )
    (net (code "19") (name "/IN_CH") (class "Default")
      (node (ref "C40") (pin "2") (pinfunction "2_2") (pintype "passive"))
      (node (ref "R36") (pin "2") (pintype "passive"))
      (node (ref "U6") (pin "1") (pinfunction "INA_1") (pintype "passive"))
    )
    (net (code "20") (name "/IN_CL") (class "Default")
      (node (ref "C45") (pin "2") (pinfunction "2_2") (pintype "passive"))
      (node (ref "R41") (pin "2") (pintype "passive"))
      (node (ref "U6") (pin "2") (pinfunction "INB_2") (pintype "passive"))
    )
    (net (code "21") (name "/POT") (class "Default")
      (node (ref "J1") (pin "18") (pinfunction "18_18") (pintype "passive"))
      (node (ref "J3") (pin "2") (pinfunction "2_2") (pintype "passive"))
    )
    (net (code "22") (name "/PWM_AH") (class "Default")
      (node (ref "J1") (pin "23") (pinfunction "23_23") (pintype "passive"))
      (node (ref "R7") (pin "1") (pintype "passive"))
    )
    (net (code "23") (name "/PWM_AL") (class "Default")
      (node (ref "J1") (pin "21") (pinfunction "21_21") (pintype "passive"))
      (node (ref "R13") (pin "1") (pintype "passive"))
    )
    (net (code "24") (name "/PWM_BH") (class "Default")
      (node (ref "J1") (pin "13") (pinfunction "13_13") (pintype "passive"))
      (node (ref "R21") (pin "1") (pintype "passive"))
    )
    (net (code "25") (name "/PWM_BL") (class "Default")
      (node (ref "J1") (pin "11") (pinfunction "11_11") (pintype "passive"))
      (node (ref "R27") (pin "1") (pintype "passive"))
    )
    (net (code "26") (name "/PWM_CH") (class "Default")
      (node (ref "J1") (pin "3") (pinfunction "3_3") (pintype "passive"))
      (node (ref "R36") (pin "1") (pintype "passive"))
    )
    (net (code "27") (name "/PWM_CL") (class "Default")
      (node (ref "J1") (pin "1") (pinfunction "1_1") (pintype "passive"))
      (node (ref "R41") (pin "1") (pintype "passive"))
    )
    (net (code "28") (name "/Sense_P") (class "Default")
      (node (ref "C30") (pin "1") (pinfunction "1_1") (pintype "passive"))
      (node (ref "C31") (pin "1") (pinfunction "1_1") (pintype "passive"))
      (node (ref "C32") (pin "1") (pinfunction "1_1") (pintype "passive"))
      (node (ref "J1") (pin "5") (pinfunction "5_5") (pintype "passive"))
      (node (ref "Q7") (pin "3") (pinfunction "S_3") (pintype "passive"))
      (node (ref "Q8") (pin "3") (pinfunction "S_3") (pintype "passive"))
      (node (ref "R26") (pin "1") (pintype "passive"))
      (node (ref "R51") (pin "2") (pinfunction "2_2") (pintype "passive"))
      (node (ref "R54") (pin "1") (pinfunction "1_1") (pintype "passive"))
      (node (ref "R55") (pin "2") (pinfunction "2_2") (pintype "passive"))
      (node (ref "U4") (pin "9") (pinfunction "VSSB_9") (pintype "passive"))
    )
    (net (code "29") (name "/VSS_A") (class "Default")
      (node (ref "C8") (pin "1") (pinfunction "1_1") (pintype "passive"))
      (node (ref "Q1") (pin "3") (pinfunction "S_3") (pintype "passive"))
      (node (ref "Q2") (pin "3") (pinfunction "S_3") (pintype "passive"))
      (node (ref "Q3") (pin "2") (pinfunction "D_2") (pintype "passive"))
      (node (ref "Q4") (pin "2") (pinfunction "D_2") (pintype "passive"))
      (node (ref "R6") (pin "1") (pintype "passive"))
      (node (ref "U1") (pin "5") (pinfunction "+VOUT_5") (pintype "passive"))
      (node (ref "U2") (pin "14") (pinfunction "VSSA_14") (pintype "passive"))
    )
    (net (code "30") (name "/VSS_B") (class "Default")
      (node (ref "C25") (pin "1") (pinfunction "1_1") (pintype "passive"))
      (node (ref "Q5") (pin "3") (pinfunction "S_3") (pintype "passive"))
      (node (ref "Q6") (pin "3") (pinfunction "S_3") (pintype "passive"))
      (node (ref "Q7") (pin "2") (pinfunction "D_2") (pintype "passive"))
      (node (ref "Q8") (pin "2") (pinfunction "D_2") (pintype "passive"))
      (node (ref "R20") (pin "1") (pintype "passive"))
      (node (ref "U3") (pin "5") (pinfunction "+VOUT_5") (pintype "passive"))
      (node (ref "U4") (pin "14") (pinfunction "VSSA_14") (pintype "passive"))
    )
    (net (code "31") (name "/VSS_C") (class "Default")
      (node (ref "C37") (pin "1") (pinfunction "1_1") (pintype "passive"))
      (node (ref "Q10") (pin "3") (pinfunction "S_3") (pintype "passive"))
      (node (ref "Q11") (pin "2") (pinfunction "D_2") (pintype "passive"))
      (node (ref "Q12") (pin "2") (pinfunction "D_2") (pintype "passive"))
      (node (ref "Q9") (pin "3") (pinfunction "S_3") (pintype "passive"))
      (node (ref "R34") (pin "1") (pintype "passive"))
      (node (ref "U5") (pin "5") (pinfunction "+VOUT_5") (pintype "passive"))
      (node (ref "U6") (pin "14") (pinfunction "VSSA_14") (pintype "passive"))
    )
    (net (code "32") (name "15V") (class "Default")
      (node (ref "C1") (pin "1") (pinfunction "1_1") (pintype "passive"))
      (node (ref "C10") (pin "2") (pinfunction "2_2") (pintype "passive"))
      (node (ref "C17") (pin "2") (pinfunction "2_2") (pintype "passive"))
      (node (ref "C18") (pin "2") (pinfunction "2_2") (pintype "passive"))
      (node (ref "C19") (pin "2") (pinfunction "2_2") (pintype "passive"))
      (node (ref "C22") (pin "1") (pinfunction "1_1") (pintype "passive"))
      (node (ref "C26") (pin "2") (pinfunction "2_2") (pintype "passive"))
      (node (ref "C27") (pin "2") (pinfunction "2_2") (pintype "passive"))
      (node (ref "C30") (pin "2") (pinfunction "2_2") (pintype "passive"))
      (node (ref "C31") (pin "2") (pinfunction "2_2") (pintype "passive"))
      (node (ref "C32") (pin "2") (pinfunction "2_2") (pintype "passive"))
      (node (ref "C34") (pin "1") (pinfunction "1_1") (pintype "passive"))
      (node (ref "C38") (pin "2") (pinfunction "2_2") (pintype "passive"))
      (node (ref "C39") (pin "2") (pinfunction "2_2") (pintype "passive"))
      (node (ref "C42") (pin "2") (pinfunction "2_2") (pintype "passive"))
      (node (ref "C43") (pin "2") (pinfunction "2_2") (pintype "passive"))
      (node (ref "C44") (pin "2") (pinfunction "2_2") (pintype "passive"))
      (node (ref "C9") (pin "2") (pinfunction "2_2") (pintype "passive"))
      (node (ref "J1") (pin "10") (pinfunction "10_10") (pintype "passive"))
      (node (ref "J1") (pin "12") (pinfunction "12_12") (pintype "passive"))
      (node (ref "J1") (pin "14") (pinfunction "14_14") (pintype "passive"))
      (node (ref "J1") (pin "4") (pinfunction "4_4") (pintype "passive"))
      (node (ref "R19") (pin "1") (pintype "passive"))
      (node (ref "R33") (pin "1") (pintype "passive"))
      (node (ref "R5") (pin "1") (pintype "passive"))
      (node (ref "U1") (pin "2") (pinfunction "+VIN_2") (pintype "passive"))
      (node (ref "U2") (pin "11") (pinfunction "VDDB_11") (pintype "passive"))
      (node (ref "U2") (pin "3") (pinfunction "VCCI_3") (pintype "passive"))
      (node (ref "U2") (pin "8") (pinfunction "VCCI_8") (pintype "passive"))
      (node (ref "U3") (pin "2") (pinfunction "+VIN_2") (pintype "passive"))
      (node (ref "U4") (pin "11") (pinfunction "VDDB_11") (pintype "passive"))
      (node (ref "U4") (pin "3") (pinfunction "VCCI_3") (pintype "passive"))
      (node (ref "U4") (pin "8") (pinfunction "VCCI_8") (pintype "passive"))
      (node (ref "U5") (pin "2") (pinfunction "+VIN_2") (pintype "passive"))
      (node (ref "U6") (pin "11") (pinfunction "VDDB_11") (pintype "passive"))
      (node (ref "U6") (pin "3") (pinfunction "VCCI_3") (pintype "passive"))
      (node (ref "U6") (pin "8") (pinfunction "VCCI_8") (pintype "passive"))
    )
    (net (code "33") (name "GND") (class "Default")
      (node (ref "C1") (pin "2") (pinfunction "2_2") (pintype "passive"))
      (node (ref "C10") (pin "1") (pinfunction "1_1") (pintype "passive"))
      (node (ref "C11") (pin "2") (pinfunction "2_2") (pintype "passive"))
      (node (ref "C12") (pin "2") (pinfunction "2_2") (pintype "passive"))
      (node (ref "C13") (pin "2") (pinfunction "2_2") (pintype "passive"))
      (node (ref "C14") (pin "2") (pinfunction "2_2") (pintype "passive"))
      (node (ref "C15") (pin "1") (pinfunction "1_1") (pintype "passive"))
      (node (ref "C16") (pin "1") (pinfunction "1_1") (pintype "passive"))
      (node (ref "C2") (pin "1") (pinfunction "1_1") (pintype "passive"))
      (node (ref "C20") (pin "1") (pinfunction "1_1") (pintype "passive"))
      (node (ref "C21") (pin "1") (pinfunction "1_1") (pintype "passive"))
      (node (ref "C22") (pin "2") (pinfunction "2_2") (pintype "passive"))
      (node (ref "C23") (pin "1") (pinfunction "1_1") (pintype "passive"))
      (node (ref "C24") (pin "1") (pinfunction "1_1") (pintype "passive"))
      (node (ref "C26") (pin "1") (pinfunction "1_1") (pintype "passive"))
      (node (ref "C27") (pin "1") (pinfunction "1_1") (pintype "passive"))
      (node (ref "C28") (pin "1") (pinfunction "1_1") (pintype "passive"))
      (node (ref "C29") (pin "1") (pinfunction "1_1") (pintype "passive"))
      (node (ref "C3") (pin "1") (pinfunction "1_1") (pintype "passive"))
      (node (ref "C33") (pin "1") (pinfunction "1_1") (pintype "passive"))
      (node (ref "C34") (pin "2") (pinfunction "2_2") (pintype "passive"))
      (node (ref "C35") (pin "1") (pinfunction "1_1") (pintype "passive"))
      (node (ref "C36") (pin "1") (pinfunction "1_1") (pintype "passive"))
      (node (ref "C38") (pin "1") (pinfunction "1_1") (pintype "passive"))
      (node (ref "C39") (pin "1") (pinfunction "1_1") (pintype "passive"))
      (node (ref "C4") (pin "2") (pinfunction "2_2") (pintype "passive"))
      (node (ref "C40") (pin "1") (pinfunction "1_1") (pintype "passive"))
      (node (ref "C41") (pin "1") (pinfunction "1_1") (pintype "passive"))
      (node (ref "C45") (pin "1") (pinfunction "1_1") (pintype "passive"))
      (node (ref "C5") (pin "2") (pinfunction "2_2") (pintype "passive"))
      (node (ref "C6") (pin "2") (pinfunction "2_2") (pintype "passive"))
      (node (ref "C7") (pin "2") (pinfunction "2_2") (pintype "passive"))
      (node (ref "C9") (pin "1") (pinfunction "1_1") (pintype "passive"))
      (node (ref "J1") (pin "20") (pinfunction "20_20") (pintype "passive"))
      (node (ref "J1") (pin "22") (pinfunction "22_22") (pintype "passive"))
      (node (ref "J1") (pin "7") (pinfunction "7_7") (pintype "passive"))
      (node (ref "J2") (pin "5") (pinfunction "5_5") (pintype "passive"))
      (node (ref "J3") (pin "3") (pinfunction "3_3") (pintype "passive"))
      (node (ref "P1") (pin "2") (pinfunction "2_2") (pintype "passive"))
      (node (ref "P2") (pin "2") (pinfunction "2_2") (pintype "passive"))
      (node (ref "P3") (pin "2") (pinfunction "2_2") (pintype "passive"))
      (node (ref "P4") (pin "2") (pinfunction "2_2") (pintype "passive"))
      (node (ref "R14") (pin "1") (pintype "passive"))
      (node (ref "R28") (pin "1") (pintype "passive"))
      (node (ref "R42") (pin "1") (pintype "passive"))
      (node (ref "R54") (pin "2") (pinfunction "2_2") (pintype "passive"))
      (node (ref "U1") (pin "1") (pinfunction "-VIN_1") (pintype "passive"))
      (node (ref "U2") (pin "4") (pinfunction "GND_4") (pintype "passive"))
      (node (ref "U2") (pin "5") (pinfunction "DISABLE_5") (pintype "passive"))
      (node (ref "U3") (pin "1") (pinfunction "-VIN_1") (pintype "passive"))
      (node (ref "U4") (pin "4") (pinfunction "GND_4") (pintype "passive"))
      (node (ref "U4") (pin "5") (pinfunction "DISABLE_5") (pintype "passive"))
      (node (ref "U5") (pin "1") (pinfunction "-VIN_1") (pintype "passive"))
      (node (ref "U6") (pin "4") (pinfunction "GND_4") (pintype "passive"))
      (node (ref "U6") (pin "5") (pinfunction "DISABLE_5") (pintype "passive"))
    )
    (net (code "34") (name "Net-(D1-Pad1)") (class "Default")
      (node (ref "D1") (pin "1") (pinfunction "1_1") (pintype "passive"))
      (node (ref "R2") (pin "2") (pintype "passive"))
      (node (ref "R3") (pin "1") (pintype "passive"))
      (node (ref "R4") (pin "1") (pintype "passive"))
      (node (ref "R6") (pin "2") (pintype "passive"))
    )
    (net (code "35") (name "Net-(D1-Pad2)") (class "Default")
      (node (ref "D1") (pin "2") (pinfunction "2_2") (pintype "passive"))
      (node (ref "R1") (pin "2") (pintype "passive"))
    )
    (net (code "36") (name "Net-(D2-Pad1)") (class "Default")
      (node (ref "D2") (pin "1") (pinfunction "1_1") (pintype "passive"))
      (node (ref "R5") (pin "2") (pintype "passive"))
    )
    (net (code "37") (name "Net-(D3-Pad1)") (class "Default")
      (node (ref "D3") (pin "1") (pinfunction "1_1") (pintype "passive"))
      (node (ref "R10") (pin "1") (pintype "passive"))
      (node (ref "R11") (pin "1") (pintype "passive"))
      (node (ref "R12") (pin "2") (pintype "passive"))
      (node (ref "R9") (pin "2") (pintype "passive"))
    )
    (net (code "38") (name "Net-(D3-Pad2)") (class "Default")
      (node (ref "D3") (pin "2") (pinfunction "2_2") (pintype "passive"))
      (node (ref "R8") (pin "2") (pintype "passive"))
    )
    (net (code "39") (name "Net-(D4-Pad1)") (class "Default")
      (node (ref "D4") (pin "1") (pinfunction "1_1") (pintype "passive"))
      (node (ref "R16") (pin "2") (pintype "passive"))
      (node (ref "R17") (pin "1") (pintype "passive"))
      (node (ref "R18") (pin "1") (pintype "passive"))
      (node (ref "R20") (pin "2") (pintype "passive"))
    )
    (net (code "40") (name "Net-(D4-Pad2)") (class "Default")
      (node (ref "D4") (pin "2") (pinfunction "2_2") (pintype "passive"))
      (node (ref "R15") (pin "2") (pintype "passive"))
    )
    (net (code "41") (name "Net-(D5-Pad1)") (class "Default")
      (node (ref "D5") (pin "1") (pinfunction "1_1") (pintype "passive"))
      (node (ref "R19") (pin "2") (pintype "passive"))
    )
    (net (code "42") (name "Net-(D6-Pad1)") (class "Default")
      (node (ref "D6") (pin "1") (pinfunction "1_1") (pintype "passive"))
      (node (ref "R23") (pin "2") (pintype "passive"))
      (node (ref "R24") (pin "1") (pintype "passive"))
      (node (ref "R25") (pin "1") (pintype "passive"))
      (node (ref "R26") (pin "2") (pintype "passive"))
    )
    (net (code "43") (name "Net-(D6-Pad2)") (class "Default")
      (node (ref "D6") (pin "2") (pinfunction "2_2") (pintype "passive"))
      (node (ref "R22") (pin "2") (pintype "passive"))
    )
    (net (code "44") (name "Net-(D7-Pad1)") (class "Default")
      (node (ref "D7") (pin "1") (pinfunction "1_1") (pintype "passive"))
      (node (ref "R30") (pin "2") (pintype "passive"))
      (node (ref "R31") (pin "1") (pintype "passive"))
      (node (ref "R32") (pin "1") (pintype "passive"))
      (node (ref "R34") (pin "2") (pintype "passive"))
    )
    (net (code "45") (name "Net-(D7-Pad2)") (class "Default")
      (node (ref "D7") (pin "2") (pinfunction "2_2") (pintype "passive"))
      (node (ref "R29") (pin "2") (pintype "passive"))
    )
    (net (code "46") (name "Net-(D8-Pad1)") (class "Default")
      (node (ref "D8") (pin "1") (pinfunction "1_1") (pintype "passive"))
      (node (ref "R33") (pin "2") (pintype "passive"))
    )
    (net (code "47") (name "Net-(D9-Pad1)") (class "Default")
      (node (ref "D9") (pin "1") (pinfunction "1_1") (pintype "passive"))
      (node (ref "R37") (pin "2") (pintype "passive"))
      (node (ref "R38") (pin "1") (pintype "passive"))
      (node (ref "R39") (pin "1") (pintype "passive"))
      (node (ref "R40") (pin "2") (pintype "passive"))
    )
    (net (code "48") (name "Net-(D9-Pad2)") (class "Default")
      (node (ref "D9") (pin "2") (pinfunction "2_2") (pintype "passive"))
      (node (ref "R35") (pin "2") (pintype "passive"))
    )
    (net (code "49") (name "Net-(Q1-G)") (class "Default")
      (node (ref "Q1") (pin "1") (pinfunction "G_1") (pintype "passive"))
      (node (ref "R3") (pin "2") (pintype "passive"))
    )
    (net (code "50") (name "Net-(Q2-G)") (class "Default")
      (node (ref "Q2") (pin "1") (pinfunction "G_1") (pintype "passive"))
      (node (ref "R4") (pin "2") (pintype "passive"))
    )
    (net (code "51") (name "Net-(Q3-G)") (class "Default")
      (node (ref "Q3") (pin "1") (pinfunction "G_1") (pintype "passive"))
      (node (ref "R10") (pin "2") (pintype "passive"))
    )
    (net (code "52") (name "Net-(Q3-S)") (class "Default")
      (node (ref "C17") (pin "1") (pinfunction "1_1") (pintype "passive"))
      (node (ref "C18") (pin "1") (pinfunction "1_1") (pintype "passive"))
      (node (ref "C19") (pin "1") (pinfunction "1_1") (pintype "passive"))
      (node (ref "Q3") (pin "3") (pinfunction "S_3") (pintype "passive"))
      (node (ref "Q4") (pin "3") (pinfunction "S_3") (pintype "passive"))
      (node (ref "R12") (pin "1") (pintype "passive"))
      (node (ref "R51") (pin "1") (pinfunction "1_1") (pintype "passive"))
      (node (ref "U2") (pin "9") (pinfunction "VSSB_9") (pintype "passive"))
    )
    (net (code "53") (name "Net-(Q4-G)") (class "Default")
      (node (ref "Q4") (pin "1") (pinfunction "G_1") (pintype "passive"))
      (node (ref "R11") (pin "2") (pintype "passive"))
    )
    (net (code "54") (name "Net-(Q5-G)") (class "Default")
      (node (ref "Q5") (pin "1") (pinfunction "G_1") (pintype "passive"))
      (node (ref "R17") (pin "2") (pintype "passive"))
    )
    (net (code "55") (name "Net-(Q6-G)") (class "Default")
      (node (ref "Q6") (pin "1") (pinfunction "G_1") (pintype "passive"))
      (node (ref "R18") (pin "2") (pintype "passive"))
    )
    (net (code "56") (name "Net-(Q7-G)") (class "Default")
      (node (ref "Q7") (pin "1") (pinfunction "G_1") (pintype "passive"))
      (node (ref "R24") (pin "2") (pintype "passive"))
    )
    (net (code "57") (name "Net-(Q8-G)") (class "Default")
      (node (ref "Q8") (pin "1") (pinfunction "G_1") (pintype "passive"))
      (node (ref "R25") (pin "2") (pintype "passive"))
    )
    (net (code "58") (name "Net-(Q9-G)") (class "Default")
      (node (ref "Q9") (pin "1") (pinfunction "G_1") (pintype "passive"))
      (node (ref "R31") (pin "2") (pintype "passive"))
    )
    (net (code "59") (name "Net-(Q10-G)") (class "Default")
      (node (ref "Q10") (pin "1") (pinfunction "G_1") (pintype "passive"))
      (node (ref "R32") (pin "2") (pintype "passive"))
    )
    (net (code "60") (name "Net-(Q11-G)") (class "Default")
      (node (ref "Q11") (pin "1") (pinfunction "G_1") (pintype "passive"))
      (node (ref "R38") (pin "2") (pintype "passive"))
    )
    (net (code "61") (name "Net-(Q11-S)") (class "Default")
      (node (ref "C42") (pin "1") (pinfunction "1_1") (pintype "passive"))
      (node (ref "C43") (pin "1") (pinfunction "1_1") (pintype "passive"))
      (node (ref "C44") (pin "1") (pinfunction "1_1") (pintype "passive"))
      (node (ref "Q11") (pin "3") (pinfunction "S_3") (pintype "passive"))
      (node (ref "Q12") (pin "3") (pinfunction "S_3") (pintype "passive"))
      (node (ref "R40") (pin "1") (pintype "passive"))
      (node (ref "R55") (pin "1") (pinfunction "1_1") (pintype "passive"))
      (node (ref "U6") (pin "9") (pinfunction "VSSB_9") (pintype "passive"))
    )
    (net (code "62") (name "Net-(Q12-G)") (class "Default")
      (node (ref "Q12") (pin "1") (pinfunction "G_1") (pintype "passive"))
      (node (ref "R39") (pin "2") (pintype "passive"))
    )
    (net (code "63") (name "Net-(U1--VOUT)") (class "Default")
      (node (ref "C8") (pin "2") (pinfunction "2_2") (pintype "passive"))
      (node (ref "D2") (pin "2") (pinfunction "2_2") (pintype "passive"))
      (node (ref "U1") (pin "4") (pinfunction "-VOUT_4") (pintype "passive"))
      (node (ref "U2") (pin "16") (pinfunction "VDDA_16") (pintype "passive"))
    )
    (net (code "64") (name "Net-(U2-DT)") (class "Default")
      (node (ref "C16") (pin "2") (pinfunction "2_2") (pintype "passive"))
      (node (ref "R14") (pin "2") (pintype "passive"))
      (node (ref "U2") (pin "6") (pinfunction "DT_6") (pintype "passive"))
    )
    (net (code "65") (name "Net-(U3--VOUT)") (class "Default")
      (node (ref "C25") (pin "2") (pinfunction "2_2") (pintype "passive"))
      (node (ref "D5") (pin "2") (pinfunction "2_2") (pintype "passive"))
      (node (ref "U3") (pin "4") (pinfunction "-VOUT_4") (pintype "passive"))
      (node (ref "U4") (pin "16") (pinfunction "VDDA_16") (pintype "passive"))
    )
    (net (code "66") (name "Net-(U4-DT)") (class "Default")
      (node (ref "C29") (pin "2") (pinfunction "2_2") (pintype "passive"))
      (node (ref "R28") (pin "2") (pintype "passive"))
      (node (ref "U4") (pin "6") (pinfunction "DT_6") (pintype "passive"))
    )
    (net (code "67") (name "Net-(U5--VOUT)") (class "Default")
      (node (ref "C37") (pin "2") (pinfunction "2_2") (pintype "passive"))
      (node (ref "D8") (pin "2") (pinfunction "2_2") (pintype "passive"))
      (node (ref "U5") (pin "4") (pinfunction "-VOUT_4") (pintype "passive"))
      (node (ref "U6") (pin "16") (pinfunction "VDDA_16") (pintype "passive"))
    )
    (net (code "68") (name "Net-(U6-DT)") (class "Default")
      (node (ref "C41") (pin "2") (pinfunction "2_2") (pintype "passive"))
      (node (ref "R42") (pin "2") (pintype "passive"))
      (node (ref "U6") (pin "6") (pinfunction "DT_6") (pintype "passive"))
    )
    (net (code "69") (name "unconnected-(U2-NC-Pad7)") (class "Default")
      (node (ref "U2") (pin "7") (pinfunction "NC_7") (pintype "passive+no_connect"))
    )
    (net (code "70") (name "unconnected-(U2-NC-Pad12)") (class "Default")
      (node (ref "U2") (pin "12") (pinfunction "NC_12") (pintype "passive+no_connect"))
    )
    (net (code "71") (name "unconnected-(U2-NC-Pad13)") (class "Default")
      (node (ref "U2") (pin "13") (pinfunction "NC_13") (pintype "passive+no_connect"))
    )
    (net (code "72") (name "unconnected-(U4-NC-Pad7)") (class "Default")
      (node (ref "U4") (pin "7") (pinfunction "NC_7") (pintype "passive+no_connect"))
    )
    (net (code "73") (name "unconnected-(U4-NC-Pad12)") (class "Default")
      (node (ref "U4") (pin "12") (pinfunction "NC_12") (pintype "passive+no_connect"))
    )
    (net (code "74") (name "unconnected-(U4-NC-Pad13)") (class "Default")
      (node (ref "U4") (pin "13") (pinfunction "NC_13") (pintype "passive+no_connect"))
    )
    (net (code "75") (name "unconnected-(U6-NC-Pad7)") (class "Default")
      (node (ref "U6") (pin "7") (pinfunction "NC_7") (pintype "passive+no_connect"))
    )
    (net (code "76") (name "unconnected-(U6-NC-Pad12)") (class "Default")
      (node (ref "U6") (pin "12") (pinfunction "NC_12") (pintype "passive+no_connect"))
    )
    (net (code "77") (name "unconnected-(U6-NC-Pad13)") (class "Default")
      (node (ref "U6") (pin "13") (pinfunction "NC_13") (pintype "passive+no_connect"))
    )
  )
)
